# Radio.net
KiCad netlist of a schematic drawn in Altium Designer
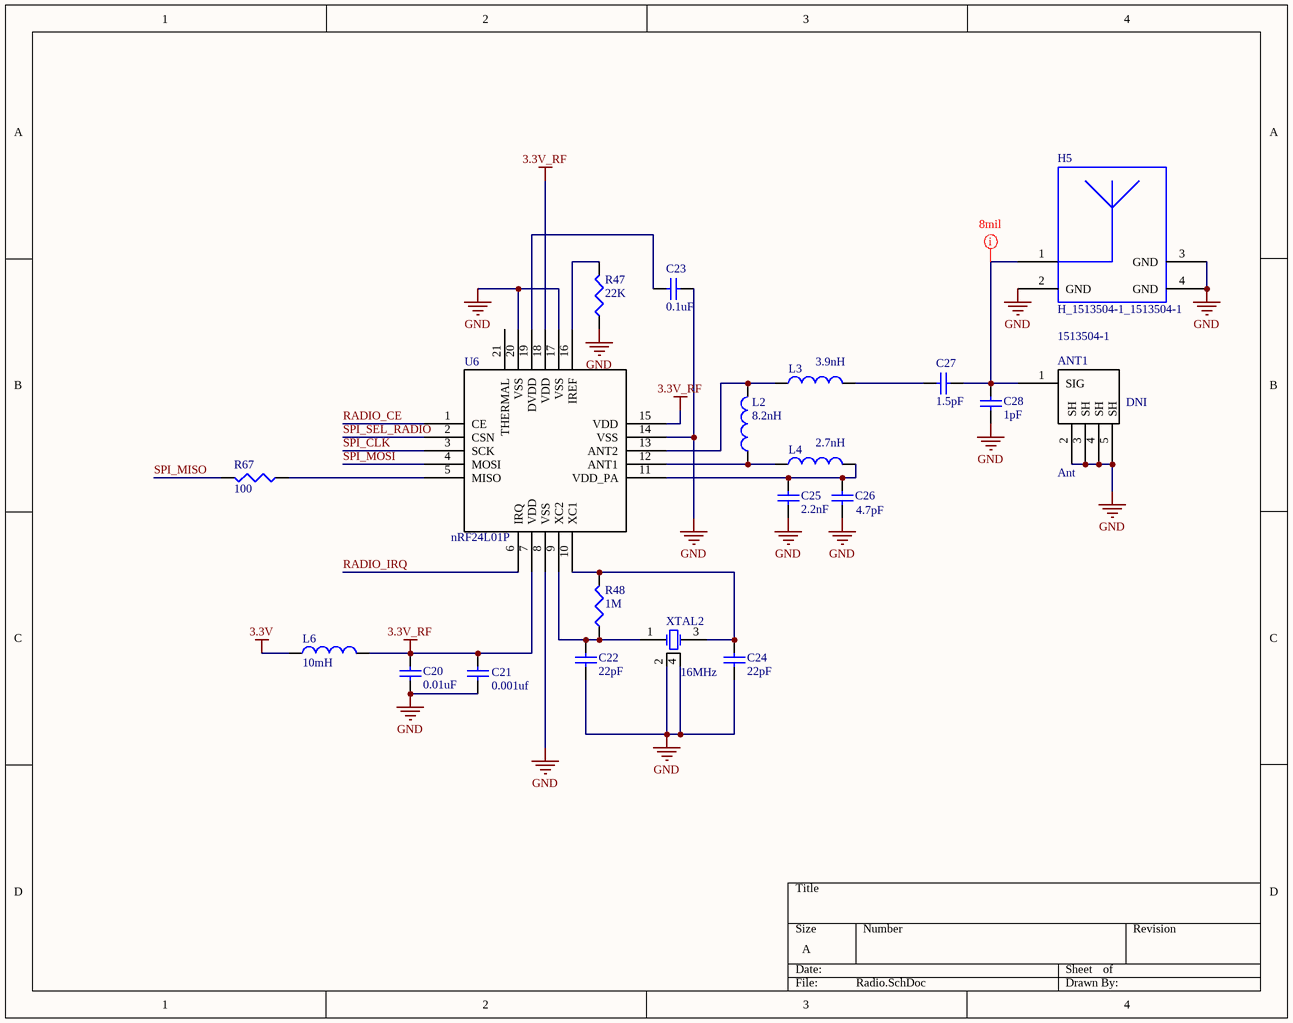
[diagram p0: Radio.SchDoc]

(export (version "E")
  (design (tool "Eeschema 10.0.6"))
  (components
    (comp (ref "ANT1")
      (value "Ant")
      (footprint "AntennaSMA")
      (fields (field (name "DNI") "DNI"))
      (libsource (lib "mrone") (part "AntennaConn"))
    )
    (comp (ref "C20")
      (value "0.01uF")
      (footprint "CAPC1005L")
      (description "Capacitor (Semiconductor SIM Model)")
      (fields
        (field (name "PART NUMBER") "C1005X7R1C103K050BA")
        (field (name "MANUFACTURER") "TDK")
        (field (name "PUBLISHER") "Altium Limited")
      )
      (libsource (lib "Miscellaneous Devices") (part "Cap Semi"))
    )
    (comp (ref "C21")
      (value "0.001uf")
      (footprint "CAPC1005L")
      (description "Capacitor (Semiconductor SIM Model)")
      (fields
        (field (name "PART NUMBER") "CC0402KRX7R7BB102")
        (field (name "MANUFACTURER") "Yageo")
        (field (name "PUBLISHER") "Altium Limited")
      )
      (libsource (lib "Miscellaneous Devices") (part "Cap Semi"))
    )
    (comp (ref "C22")
      (value "22pF")
      (footprint "CAPC1005L")
      (description "Capacitor (Semiconductor SIM Model)")
      (fields
        (field (name "PART NUMBER") "GRM1555C1H220JZ01D")
        (field (name "MANUFACTURER") "Murata")
        (field (name "PUBLISHER") "Altium Limited")
      )
      (libsource (lib "Miscellaneous Devices") (part "Cap Semi"))
    )
    (comp (ref "C23")
      (value "0.1uF")
      (footprint "CAPC1005L")
      (description "Capacitor (Semiconductor SIM Model)")
      (fields
        (field (name "PART NUMBER") "C1005X5R1A104M050BA")
        (field (name "MANUFACTURER") "TDK")
        (field (name "PUBLISHER") "Altium Limited")
      )
      (libsource (lib "Miscellaneous Devices") (part "Cap Semi"))
    )
    (comp (ref "C24")
      (value "22pF")
      (footprint "CAPC1005L")
      (description "Capacitor (Semiconductor SIM Model)")
      (fields
        (field (name "PART NUMBER") "GRM1555C1H220JZ01D")
        (field (name "MANUFACTURER") "Yageo")
        (field (name "PUBLISHER") "Altium Limited")
      )
      (libsource (lib "Miscellaneous Devices") (part "Cap Semi"))
    )
    (comp (ref "C25")
      (value "2.2nF")
      (footprint "CAPC1005L")
      (description "Capacitor (Semiconductor SIM Model)")
      (fields
        (field (name "PART NUMBER") "04025C222JAT2A")
        (field (name "MANUFACTURER") "AVX")
        (field (name "PUBLISHER") "Altium Limited")
      )
      (libsource (lib "Miscellaneous Devices") (part "Cap Semi"))
    )
    (comp (ref "C26")
      (value "4.7pF")
      (footprint "CAPC1005L")
      (description "Capacitor (Semiconductor SIM Model)")
      (fields
        (field (name "PART NUMBER") "UVK105CH4R7JW-F")
        (field (name "MANUFACTURER") "Taiyo Yuden")
        (field (name "PUBLISHER") "Altium Limited")
      )
      (libsource (lib "Miscellaneous Devices") (part "Cap Semi"))
    )
    (comp (ref "C27")
      (value "1.5pF")
      (footprint "CAPC1005L")
      (description "Capacitor (Semiconductor SIM Model)")
      (fields
        (field (name "PART NUMBER") "GRM1555C1H1R5CZ01D")
        (field (name "MANUFACTURER") "Murata")
        (field (name "PUBLISHER") "Altium Limited")
      )
      (libsource (lib "Miscellaneous Devices") (part "Cap Semi"))
    )
    (comp (ref "C28")
      (value "1pF")
      (footprint "CAPC1005L")
      (description "Capacitor (Semiconductor SIM Model)")
      (fields
        (field (name "PART NUMBER") "C1005C0G1H010C")
        (field (name "MANUFACTURER") "TDK")
        (field (name "PUBLISHER") "Altium Limited")
      )
      (libsource (lib "Miscellaneous Devices") (part "Cap Semi"))
    )
    (comp (ref "H5")
      (value "H_1513504-1_1513504-1")
      (footprint "1513504-1")
      (fields (field (name "PART NUMBER") "1513504-1") (field (name "MANUFACTURER") "TE Connectivity"))
      (libsource (lib "Schlib1") (part "H_1513504-1_1513504-1"))
    )
    (comp (ref "L2")
      (value "8.2nH")
      (footprint "INDC1005AL")
      (description "Inductor")
      (fields
        (field (name "PART NUMBER") "L-07C8N2JV6T")
        (field (name "MANUFACTURER") "Johanson Technology")
        (field (name "PUBLISHER") "Altium Limited")
      )
      (libsource (lib "Miscellaneous Devices") (part "Inductor"))
    )
    (comp (ref "L3")
      (value "3.9nH")
      (footprint "INDC1005AL")
      (description "Inductor")
      (fields
        (field (name "PART NUMBER") "L-07C3N9SV6T")
        (field (name "MANUFACTURER") "Johanson Technology")
        (field (name "PUBLISHER") "Altium Limited")
      )
      (libsource (lib "Miscellaneous Devices") (part "Inductor"))
    )
    (comp (ref "L4")
      (value "2.7nH")
      (footprint "INDC1005AL")
      (description "Inductor")
      (fields
        (field (name "PART NUMBER") "L-07C2N7SV6T")
        (field (name "MANUFACTURER") "Johanson Technology")
        (field (name "PUBLISHER") "Altium Limited")
      )
      (libsource (lib "Miscellaneous Devices") (part "Inductor"))
    )
    (comp (ref "L6")
      (value "10mH")
      (footprint "INDC2012L")
      (description "Inductor")
      (fields
        (field (name "PART NUMBER") "MMZ2012R102A")
        (field (name "MANUFACTURER") "TDK")
        (field (name "PUBLISHER") "Altium Limited")
      )
      (libsource (lib "") (part "Inductor_1"))
    )
    (comp (ref "R47")
      (value "22K")
      (footprint "RESC1608L")
      (description "Resistor")
      (fields
        (field (name "PART NUMBER") "ERJ-3GEYJ223V")
        (field (name "MANUFACTURER") "Panasonic")
        (field (name "PUBLISHER") "Altium Limited")
      )
      (libsource (lib "Miscellaneous Devices") (part "Res3"))
    )
    (comp (ref "R48")
      (value "1M")
      (footprint "RESC1608L")
      (description "Resistor")
      (fields
        (field (name "PART NUMBER") "CR0603-JW-105GLF")
        (field (name "MANUFACTURER") "Bourns")
        (field (name "PUBLISHER") "Altium Limited")
      )
      (libsource (lib "Miscellaneous Devices") (part "Res3"))
    )
    (comp (ref "R67")
      (value "100")
      (footprint "RESC1608L")
      (description "Resistor")
      (fields
        (field (name "PART NUMBER") "ERJ-3GEYJ101V")
        (field (name "MANUFACTURER") "Panasonic")
        (field (name "PUBLISHER") "Altium Limited")
      )
      (libsource (lib "Miscellaneous Devices") (part "Res3"))
    )
    (comp (ref "U6")
      (value "nRF24L01P")
      (footprint "QFN-20")
      (fields (field (name "PART NUMBER") "nRF24L01+") (field (name "MANUFACTURER") "Nordic Semiconductor"))
      (libsource (lib "mrone") (part "radio-nRF24L01P"))
    )
    (comp (ref "XTAL2")
      (value "16MHz")
      (footprint "CRYSTAL")
      (fields (field (name "PART NUMBER") "ABM3B-16.000MHZ-10-1-U-T") (field (name "MANUFACTURER") "Abracon"))
      (libsource (lib "mrone") (part "Crystal"))
    )
  )
  (nets
    (net (code "1") (name "/RADIO_CE") (class "Default")
      (node (ref "U6") (pin "1") (pinfunction "CE_1") (pintype "passive"))
    )
    (net (code "2") (name "/RADIO_IRQ") (class "Default")
      (node (ref "U6") (pin "6") (pinfunction "IRQ_6") (pintype "passive"))
    )
    (net (code "3") (name "/SPI_CLK") (class "Default")
      (node (ref "U6") (pin "3") (pinfunction "SCK_3") (pintype "passive"))
    )
    (net (code "4") (name "/SPI_MISO") (class "Default")
      (node (ref "R67") (pin "2") (pinfunction "2_2") (pintype "passive"))
    )
    (net (code "5") (name "/SPI_MOSI") (class "Default")
      (node (ref "U6") (pin "4") (pinfunction "MOSI_4") (pintype "passive"))
    )
    (net (code "6") (name "/SPI_SEL_RADIO") (class "Default")
      (node (ref "U6") (pin "2") (pinfunction "CSN_2") (pintype "passive"))
    )
    (net (code "7") (name "3.3V") (class "Default")
      (node (ref "L6") (pin "2") (pinfunction "2_2") (pintype "passive"))
    )
    (net (code "8") (name "3.3V_RF") (class "Default")
      (node (ref "C20") (pin "2") (pinfunction "2_2") (pintype "passive"))
      (node (ref "C21") (pin "2") (pinfunction "2_2") (pintype "passive"))
      (node (ref "L6") (pin "1") (pinfunction "1_1") (pintype "passive"))
      (node (ref "U6") (pin "15") (pinfunction "VDD_15") (pintype "passive"))
      (node (ref "U6") (pin "18") (pinfunction "VDD_18") (pintype "passive"))
      (node (ref "U6") (pin "7") (pinfunction "VDD_7") (pintype "passive"))
    )
    (net (code "9") (name "GND") (class "Default")
      (node (ref "ANT1") (pin "2") (pinfunction "SH_2") (pintype "passive"))
      (node (ref "ANT1") (pin "3") (pinfunction "SH_3") (pintype "passive"))
      (node (ref "ANT1") (pin "4") (pinfunction "SH_4") (pintype "passive"))
      (node (ref "ANT1") (pin "5") (pinfunction "SH_5") (pintype "passive"))
      (node (ref "C20") (pin "1") (pinfunction "1_1") (pintype "passive"))
      (node (ref "C21") (pin "1") (pinfunction "1_1") (pintype "passive"))
      (node (ref "C22") (pin "1") (pinfunction "1_1") (pintype "passive"))
      (node (ref "C23") (pin "1") (pinfunction "1_1") (pintype "passive"))
      (node (ref "C24") (pin "1") (pinfunction "1_1") (pintype "passive"))
      (node (ref "C25") (pin "1") (pinfunction "1_1") (pintype "passive"))
      (node (ref "C26") (pin "1") (pinfunction "1_1") (pintype "passive"))
      (node (ref "C28") (pin "1") (pinfunction "1_1") (pintype "passive"))
      (node (ref "H5") (pin "2") (pinfunction "GND_2") (pintype "passive"))
      (node (ref "H5") (pin "3") (pinfunction "GND_3") (pintype "power_in"))
      (node (ref "H5") (pin "4") (pinfunction "GND_4") (pintype "power_in"))
      (node (ref "R47") (pin "1") (pinfunction "1_1") (pintype "passive"))
      (node (ref "U6") (pin "14") (pinfunction "VSS_14") (pintype "passive"))
      (node (ref "U6") (pin "17") (pinfunction "VSS_17") (pintype "passive"))
      (node (ref "U6") (pin "20") (pinfunction "VSS_20") (pintype "passive"))
      (node (ref "U6") (pin "8") (pinfunction "VSS_8") (pintype "passive"))
      (node (ref "XTAL2") (pin "2") (pinfunction "GND_2") (pintype "passive"))
      (node (ref "XTAL2") (pin "4") (pinfunction "GND_4") (pintype "passive"))
    )
    (net (code "10") (name "Net-(ANT1-SIG)") (class "Default")
      (node (ref "ANT1") (pin "1") (pinfunction "SIG_1") (pintype "passive"))
      (node (ref "C27") (pin "1") (pinfunction "1_1") (pintype "passive"))
      (node (ref "C28") (pin "2") (pinfunction "2_2") (pintype "passive"))
      (node (ref "H5") (pin "1") (pinfunction "1_1") (pintype "passive"))
    )
    (net (code "11") (name "Net-(C27-Pad2)") (class "Default")
      (node (ref "C27") (pin "2") (pinfunction "2_2") (pintype "passive"))
      (node (ref "L3") (pin "2") (pinfunction "2_2") (pintype "passive"))
    )
    (net (code "12") (name "Net-(U6-ANT1)") (class "Default")
      (node (ref "L2") (pin "1") (pinfunction "1_1") (pintype "passive"))
      (node (ref "L4") (pin "1") (pinfunction "1_1") (pintype "passive"))
      (node (ref "U6") (pin "12") (pinfunction "ANT1_12") (pintype "passive"))
    )
    (net (code "13") (name "Net-(U6-ANT2)") (class "Default")
      (node (ref "L2") (pin "2") (pinfunction "2_2") (pintype "passive"))
      (node (ref "L3") (pin "1") (pinfunction "1_1") (pintype "passive"))
      (node (ref "U6") (pin "13") (pinfunction "ANT2_13") (pintype "passive"))
    )
    (net (code "14") (name "Net-(U6-DVDD)") (class "Default")
      (node (ref "C23") (pin "2") (pinfunction "2_2") (pintype "passive"))
      (node (ref "U6") (pin "19") (pinfunction "DVDD_19") (pintype "passive"))
    )
    (net (code "15") (name "Net-(U6-IREF)") (class "Default")
      (node (ref "R47") (pin "2") (pinfunction "2_2") (pintype "passive"))
      (node (ref "U6") (pin "16") (pinfunction "IREF_16") (pintype "passive"))
    )
    (net (code "16") (name "Net-(U6-MISO)") (class "Default")
      (node (ref "R67") (pin "1") (pinfunction "1_1") (pintype "passive"))
      (node (ref "U6") (pin "5") (pinfunction "MISO_5") (pintype "passive"))
    )
    (net (code "17") (name "Net-(U6-VDD_PA)") (class "Default")
      (node (ref "C25") (pin "2") (pinfunction "2_2") (pintype "passive"))
      (node (ref "C26") (pin "2") (pinfunction "2_2") (pintype "passive"))
      (node (ref "L4") (pin "2") (pinfunction "2_2") (pintype "passive"))
      (node (ref "U6") (pin "11") (pinfunction "VDD_PA_11") (pintype "passive"))
    )
    (net (code "18") (name "Net-(U6-XC1)") (class "Default")
      (node (ref "C24") (pin "2") (pinfunction "2_2") (pintype "passive"))
      (node (ref "R48") (pin "2") (pinfunction "2_2") (pintype "passive"))
      (node (ref "U6") (pin "10") (pinfunction "XC1_10") (pintype "passive"))
      (node (ref "XTAL2") (pin "3") (pinfunction "OSC2_3") (pintype "passive"))
    )
    (net (code "19") (name "Net-(U6-XC2)") (class "Default")
      (node (ref "C22") (pin "2") (pinfunction "2_2") (pintype "passive"))
      (node (ref "R48") (pin "1") (pinfunction "1_1") (pintype "passive"))
      (node (ref "U6") (pin "9") (pinfunction "XC2_9") (pintype "passive"))
      (node (ref "XTAL2") (pin "1") (pinfunction "OSC1_1") (pintype "passive"))
    )
    (net (code "20") (name "unconnected-(U6-THERMAL-Pad21)") (class "Default")
      (node (ref "U6") (pin "21") (pinfunction "THERMAL_21") (pintype "passive"))
    )
  )
)
